# 07_-_eMMC.net
KiCad netlist of a schematic drawn in Altium Designer
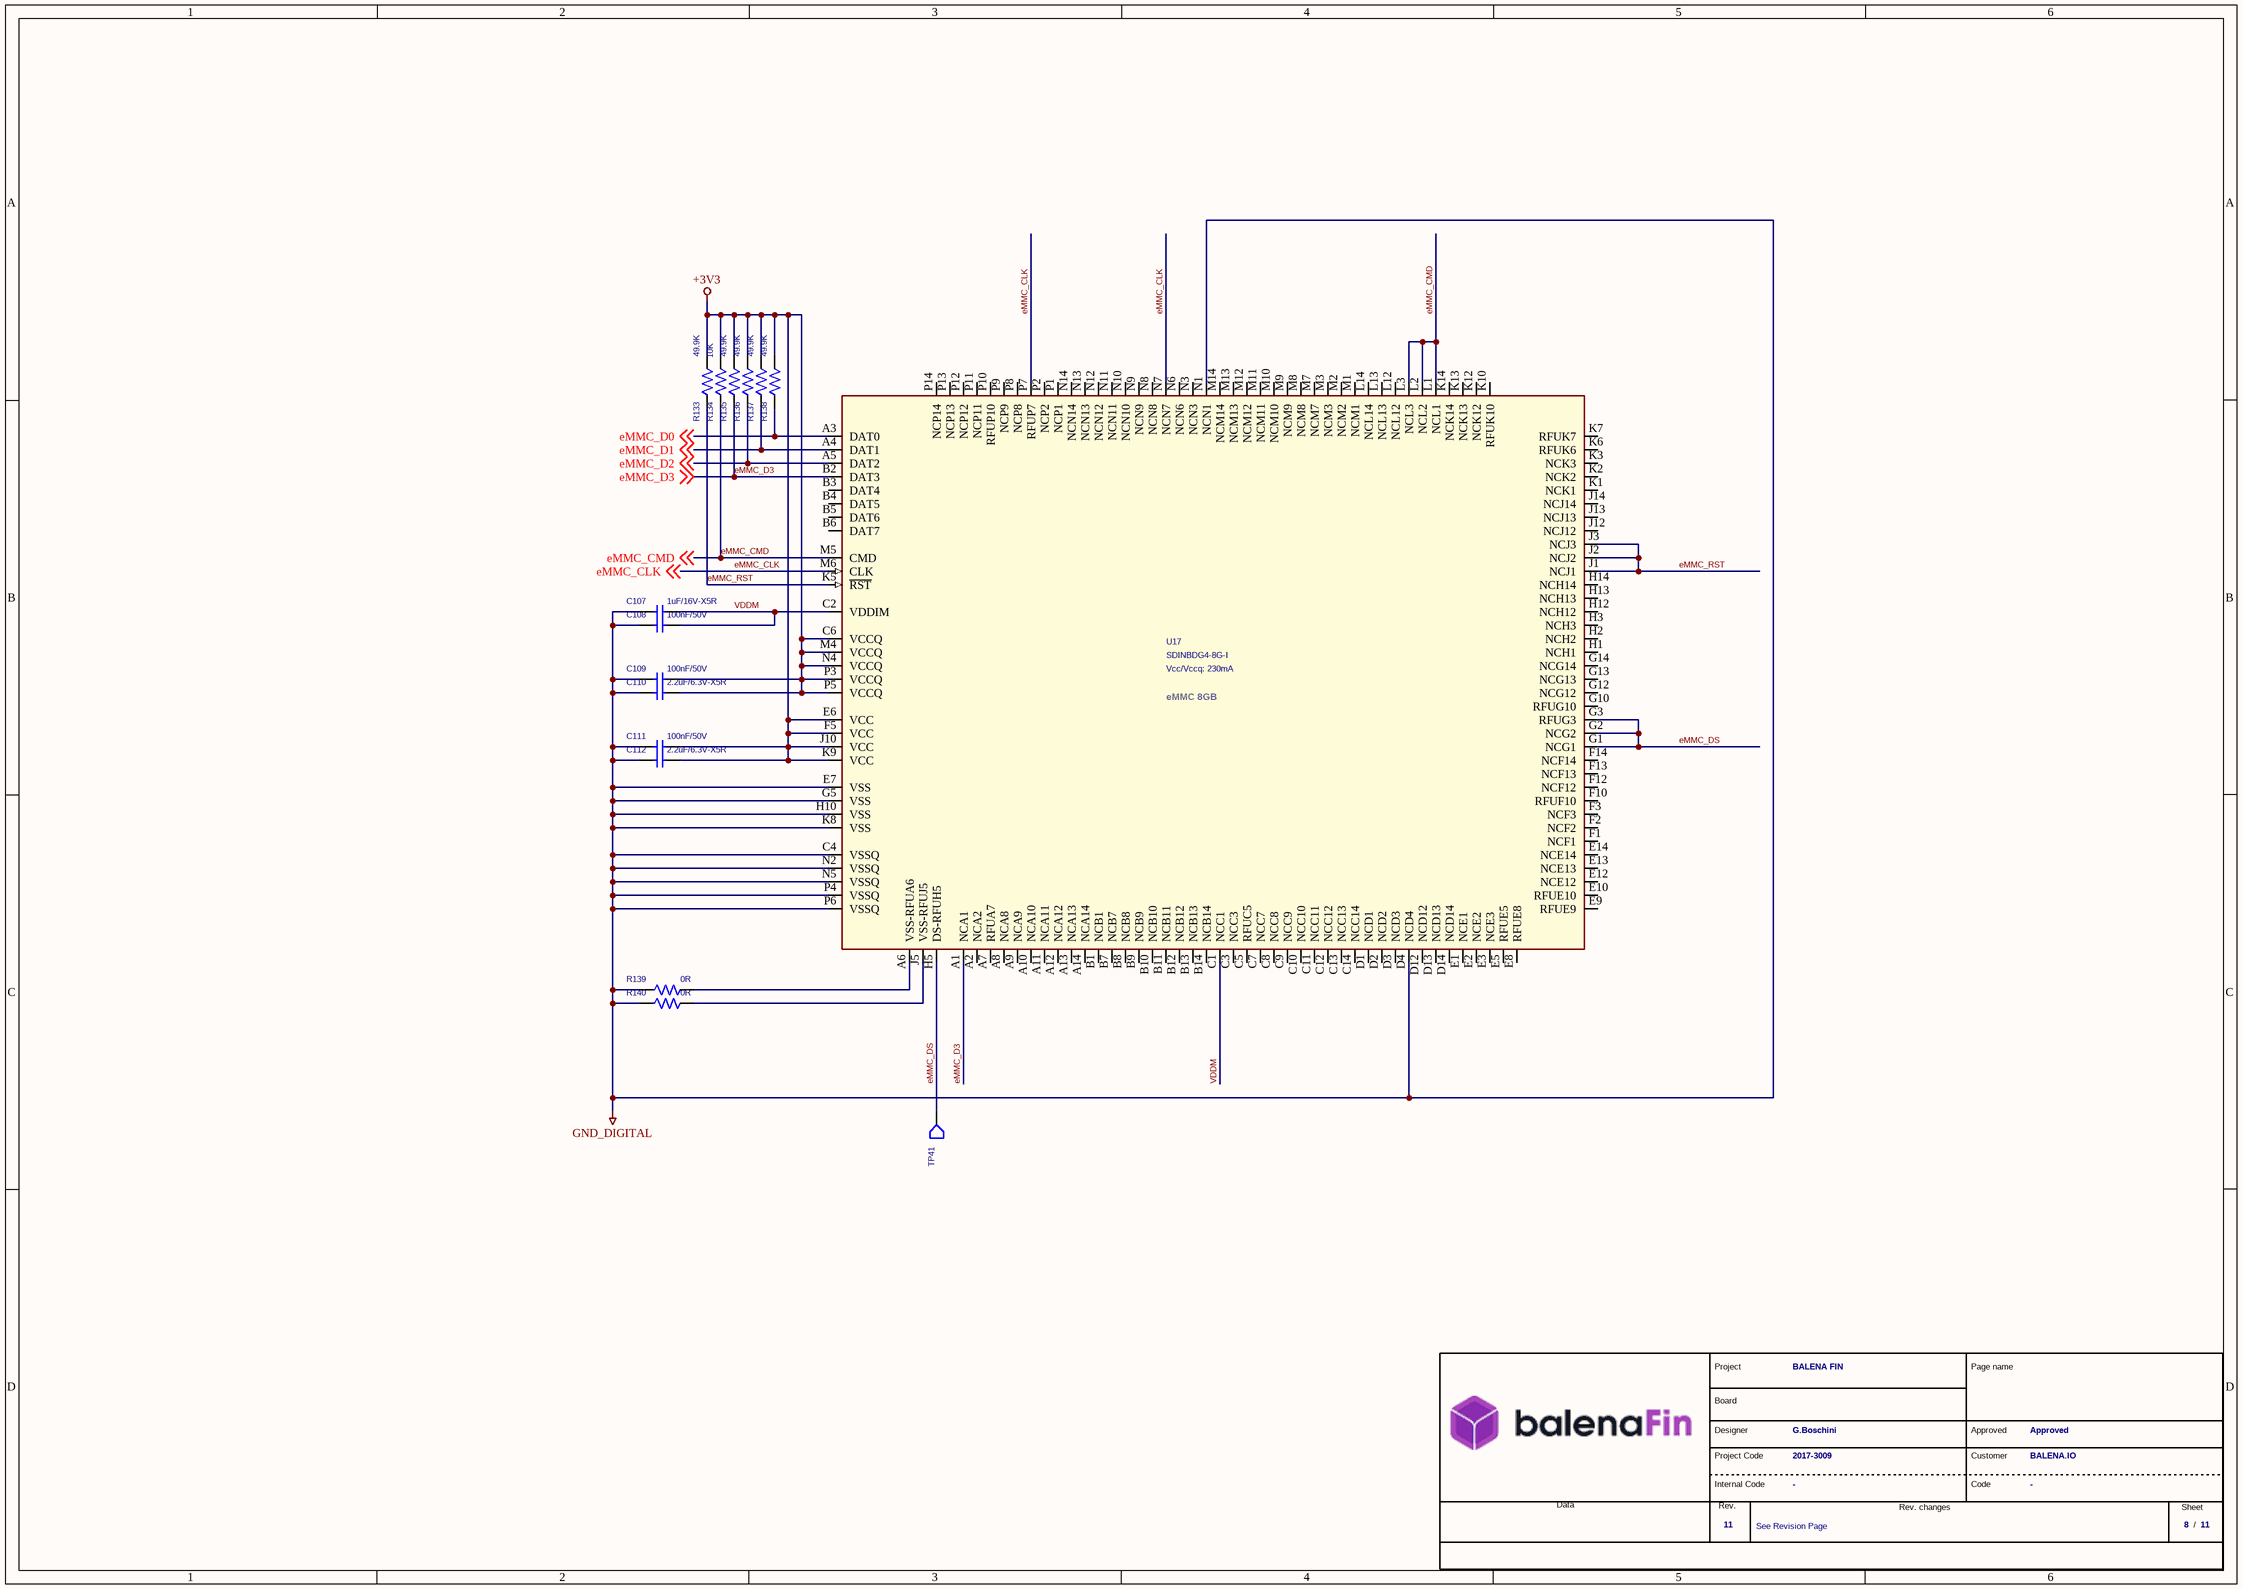
[diagram p0: 07 - eMMC.SchDoc]

(export (version "E")
  (design (tool "Eeschema 10.0.6"))
  (components
    (comp (ref "C107")
      (value "1uF/16V-X5R")
      (footprint "CS-C-0402")
      (description "CHIP CAP.CER. 1uF 16V 10% X5R 0402")
      (fields (field (name "MPN") "Generic"))
      (libsource (lib "*") (part "CS-C-0402-1u/16-X5R"))
    )
    (comp (ref "C108")
      (value "100nF/50V")
      (footprint "CS-C-0402")
      (description "CHIP CAP.CER. 100nF 16V 10% X7R 0402")
      (fields (field (name "MPN") "Generic"))
      (libsource (lib "*") (part "CS-C-0402-100n/16V"))
    )
    (comp (ref "C109")
      (value "100nF/50V")
      (footprint "CS-C-0402")
      (description "CHIP CAP.CER. 100nF 16V 10% X7R 0402")
      (fields (field (name "MPN") "Generic"))
      (libsource (lib "*") (part "CS-C-0402-100n/16V"))
    )
    (comp (ref "C110")
      (value "2.2uF/6.3V-X5R")
      (footprint "CS-C-0402")
      (description "CHIP CAP.CER. 2.2uF 6.3V 20% X5R 0402")
      (fields (field (name "MPN") "Generic"))
      (libsource (lib "*") (part "CS-C-0402-2.2u/6V3-X5R"))
    )
    (comp (ref "C111")
      (value "100nF/50V")
      (footprint "CS-C-0402")
      (description "CHIP CAP.CER. 100nF 16V 10% X7R 0402")
      (fields (field (name "MPN") "Generic"))
      (libsource (lib "*") (part "CS-C-0402-100n/16V"))
    )
    (comp (ref "C112")
      (value "2.2uF/6.3V-X5R")
      (footprint "CS-C-0402")
      (description "CHIP CAP.CER. 2.2uF 6.3V 20% X5R 0402")
      (fields (field (name "MPN") "Generic"))
      (libsource (lib "*") (part "CS-C-0402-2.2u/6V3-X5R"))
    )
    (comp (ref "R133")
      (value "49.9K")
      (footprint "RS-0402")
      (description "CHIP RES. 49K9 0402 1/16W 1% 100PPM/°C")
      (fields (field (name "MPN") "Generic"))
      (libsource (lib "*") (part "RS-0402-49.9k"))
    )
    (comp (ref "R134")
      (value "10K")
      (footprint "RS-0402")
      (description "CHIP RES. 10K 0402 1/16W 1%")
      (fields (field (name "MPN") "Generic"))
      (libsource (lib "*") (part "RS-0402-10k"))
    )
    (comp (ref "R135")
      (value "49.9K")
      (footprint "RS-0402")
      (description "CHIP RES. 49K9 0402 1/16W 1% 100PPM/°C")
      (fields (field (name "MPN") "Generic"))
      (libsource (lib "*") (part "RS-0402-49.9k"))
    )
    (comp (ref "R136")
      (value "49.9K")
      (footprint "RS-0402")
      (description "CHIP RES. 49K9 0402 1/16W 1% 100PPM/°C")
      (fields (field (name "MPN") "Generic"))
      (libsource (lib "*") (part "RS-0402-49.9k"))
    )
    (comp (ref "R137")
      (value "49.9K")
      (footprint "RS-0402")
      (description "CHIP RES. 49K9 0402 1/16W 1% 100PPM/°C")
      (fields (field (name "MPN") "Generic"))
      (libsource (lib "*") (part "RS-0402-49.9k"))
    )
    (comp (ref "R138")
      (value "49.9K")
      (footprint "RS-0402")
      (description "CHIP RES. 49K9 0402 1/16W 1% 100PPM/°C")
      (fields (field (name "MPN") "Generic"))
      (libsource (lib "*") (part "RS-0402-49.9k"))
    )
    (comp (ref "R139")
      (value "0R")
      (footprint "RS-0402")
      (description "CHIP RES. 0R 0402 1/16W 1%")
      (fields (field (name "MPN") "Generic"))
      (libsource (lib "*") (part "RS-0402-0r"))
    )
    (comp (ref "R140")
      (value "0R")
      (footprint "RS-0402")
      (description "CHIP RES. 0R 0402 1/16W 1%")
      (fields (field (name "MPN") "Generic"))
      (libsource (lib "*") (part "RS-0402-0r"))
    )
    (comp (ref "TP41")
      (value "TPS")
      (footprint "TPS-0100")
      (description "TEST POINT SMD")
      (fields (field (name "MPN") "TP-No-BoM"))
      (libsource (lib "*") (part "TEST POINT SMD 1 MM"))
    )
    (comp (ref "U17")
      (value "SDINBDG4-8G-I")
      (footprint "VFBGA153")
      (description "IC eMMC SDINBDG4-8G SANDISK VFBGA153 SMT")
      (fields (field (name "POWER REQUIREMENTS") "Vcc/Vccq: 230mA"))
      (libsource (lib "*") (part "eMMC - SDINBDG4-8G-I - 8GB"))
    )
  )
  (nets
    (net (code "1") (name "+3V3") (class "Default")
      (node (ref "C109") (pin "2") (pinfunction "2_2") (pintype "passive"))
      (node (ref "C110") (pin "2") (pinfunction "2_2") (pintype "passive"))
      (node (ref "C111") (pin "2") (pinfunction "2_2") (pintype "passive"))
      (node (ref "C112") (pin "2") (pinfunction "2_2") (pintype "passive"))
      (node (ref "R133") (pin "2") (pinfunction "2_2") (pintype "passive"))
      (node (ref "R134") (pin "2") (pinfunction "2_2") (pintype "passive"))
      (node (ref "R135") (pin "2") (pinfunction "2_2") (pintype "passive"))
      (node (ref "R136") (pin "2") (pinfunction "2_2") (pintype "passive"))
      (node (ref "R137") (pin "2") (pinfunction "2_2") (pintype "passive"))
      (node (ref "R138") (pin "2") (pinfunction "2_2") (pintype "passive"))
      (node (ref "U17") (pin "C6") (pinfunction "VCCQ_C6") (pintype "power_in"))
      (node (ref "U17") (pin "E6") (pinfunction "VCC_E6") (pintype "power_in"))
      (node (ref "U17") (pin "F5") (pinfunction "VCC_F5") (pintype "power_in"))
      (node (ref "U17") (pin "J10") (pinfunction "VCC_J10") (pintype "power_in"))
      (node (ref "U17") (pin "K9") (pinfunction "VCC_K9") (pintype "power_in"))
      (node (ref "U17") (pin "M4") (pinfunction "VCCQ_M4") (pintype "power_in"))
      (node (ref "U17") (pin "N4") (pinfunction "VCCQ_N4") (pintype "power_in"))
      (node (ref "U17") (pin "P3") (pinfunction "VCCQ_P3") (pintype "power_in"))
      (node (ref "U17") (pin "P5") (pinfunction "VCCQ_P5") (pintype "power_in"))
    )
    (net (code "2") (name "/VDDM") (class "Default")
      (node (ref "C107") (pin "2") (pinfunction "2_2") (pintype "passive"))
      (node (ref "C108") (pin "2") (pinfunction "2_2") (pintype "passive"))
      (node (ref "U17") (pin "C1") (pinfunction "NCC1_C1") (pintype "passive"))
      (node (ref "U17") (pin "C2") (pinfunction "VDDIM_C2") (pintype "passive"))
    )
    (net (code "3") (name "/eMMC_DS") (class "Default")
      (node (ref "TP41") (pin "1") (pinfunction "TP_1") (pintype "passive"))
      (node (ref "U17") (pin "G1") (pinfunction "NCG1_G1") (pintype "passive"))
      (node (ref "U17") (pin "G2") (pinfunction "NCG2_G2") (pintype "passive"))
      (node (ref "U17") (pin "G3") (pinfunction "RFUG3_G3") (pintype "passive"))
      (node (ref "U17") (pin "H5") (pinfunction "DS-RFUH5_H5") (pintype "passive"))
    )
    (net (code "4") (name "/eMMC_RST") (class "Default")
      (node (ref "R133") (pin "1") (pinfunction "1_1") (pintype "passive"))
      (node (ref "U17") (pin "J1") (pinfunction "NCJ1_J1") (pintype "passive"))
      (node (ref "U17") (pin "J2") (pinfunction "NCJ2_J2") (pintype "passive"))
      (node (ref "U17") (pin "J3") (pinfunction "NCJ3_J3") (pintype "passive"))
      (node (ref "U17") (pin "K5") (pinfunction "~{RST}_K5") (pintype "input"))
    )
    (net (code "5") (name "GND_DIGITAL") (class "Default")
      (node (ref "C107") (pin "1") (pinfunction "1_1") (pintype "passive"))
      (node (ref "C108") (pin "1") (pinfunction "1_1") (pintype "passive"))
      (node (ref "C109") (pin "1") (pinfunction "1_1") (pintype "passive"))
      (node (ref "C110") (pin "1") (pinfunction "1_1") (pintype "passive"))
      (node (ref "C111") (pin "1") (pinfunction "1_1") (pintype "passive"))
      (node (ref "C112") (pin "1") (pinfunction "1_1") (pintype "passive"))
      (node (ref "R139") (pin "1") (pinfunction "1_1") (pintype "passive"))
      (node (ref "R140") (pin "1") (pinfunction "1_1") (pintype "passive"))
      (node (ref "U17") (pin "C4") (pinfunction "VSSQ_C4") (pintype "power_in"))
      (node (ref "U17") (pin "D4") (pinfunction "NCD4_D4") (pintype "passive"))
      (node (ref "U17") (pin "E7") (pinfunction "VSS_E7") (pintype "power_in"))
      (node (ref "U17") (pin "G5") (pinfunction "VSS_G5") (pintype "power_in"))
      (node (ref "U17") (pin "H10") (pinfunction "VSS_H10") (pintype "power_in"))
      (node (ref "U17") (pin "K8") (pinfunction "VSS_K8") (pintype "power_in"))
      (node (ref "U17") (pin "N1") (pinfunction "NCN1_N1") (pintype "passive"))
      (node (ref "U17") (pin "N2") (pinfunction "VSSQ_N2") (pintype "power_in"))
      (node (ref "U17") (pin "N5") (pinfunction "VSSQ_N5") (pintype "power_in"))
      (node (ref "U17") (pin "P4") (pinfunction "VSSQ_P4") (pintype "power_in"))
      (node (ref "U17") (pin "P6") (pinfunction "VSSQ_P6") (pintype "power_in"))
    )
    (net (code "6") (name "Net-(U17-VSS-RFUA6)") (class "Default")
      (node (ref "R139") (pin "2") (pinfunction "2_2") (pintype "passive"))
      (node (ref "U17") (pin "A6") (pinfunction "VSS-RFUA6_A6") (pintype "passive"))
    )
    (net (code "7") (name "Net-(U17-VSS-RFUJ5)") (class "Default")
      (node (ref "R140") (pin "2") (pinfunction "2_2") (pintype "passive"))
      (node (ref "U17") (pin "J5") (pinfunction "VSS-RFUJ5_J5") (pintype "passive"))
    )
    (net (code "8") (name "eMMC_CLK") (class "Default")
      (node (ref "U17") (pin "M6") (pinfunction "CLK_M6") (pintype "input"))
      (node (ref "U17") (pin "N7") (pinfunction "NCN7_N7") (pintype "passive"))
      (node (ref "U17") (pin "P7") (pinfunction "RFUP7_P7") (pintype "passive"))
    )
    (net (code "9") (name "eMMC_CMD") (class "Default")
      (node (ref "R134") (pin "1") (pinfunction "1_1") (pintype "passive"))
      (node (ref "U17") (pin "L1") (pinfunction "NCL1_L1") (pintype "passive"))
      (node (ref "U17") (pin "L2") (pinfunction "NCL2_L2") (pintype "passive"))
      (node (ref "U17") (pin "L3") (pinfunction "NCL3_L3") (pintype "passive"))
      (node (ref "U17") (pin "M5") (pinfunction "CMD_M5") (pintype "bidirectional"))
    )
    (net (code "10") (name "eMMC_D0") (class "Default")
      (node (ref "R138") (pin "1") (pinfunction "1_1") (pintype "passive"))
      (node (ref "U17") (pin "A3") (pinfunction "DAT0_A3") (pintype "bidirectional"))
    )
    (net (code "11") (name "eMMC_D1") (class "Default")
      (node (ref "R137") (pin "1") (pinfunction "1_1") (pintype "passive"))
      (node (ref "U17") (pin "A4") (pinfunction "DAT1_A4") (pintype "bidirectional"))
    )
    (net (code "12") (name "eMMC_D2") (class "Default")
      (node (ref "R136") (pin "1") (pinfunction "1_1") (pintype "passive"))
      (node (ref "U17") (pin "A5") (pinfunction "DAT2_A5") (pintype "bidirectional"))
    )
    (net (code "13") (name "eMMC_D3") (class "Default")
      (node (ref "R135") (pin "1") (pinfunction "1_1") (pintype "passive"))
      (node (ref "U17") (pin "A1") (pinfunction "NCA1_A1") (pintype "passive"))
      (node (ref "U17") (pin "B2") (pinfunction "DAT3_B2") (pintype "bidirectional"))
    )
    (net (code "14") (name "unconnected-(U17-DAT4-PadB3)") (class "Default")
      (node (ref "U17") (pin "B3") (pinfunction "DAT4_B3") (pintype "bidirectional"))
    )
    (net (code "15") (name "unconnected-(U17-DAT5-PadB4)") (class "Default")
      (node (ref "U17") (pin "B4") (pinfunction "DAT5_B4") (pintype "bidirectional"))
    )
    (net (code "16") (name "unconnected-(U17-DAT6-PadB5)") (class "Default")
      (node (ref "U17") (pin "B5") (pinfunction "DAT6_B5") (pintype "bidirectional"))
    )
    (net (code "17") (name "unconnected-(U17-DAT7-PadB6)") (class "Default")
      (node (ref "U17") (pin "B6") (pinfunction "DAT7_B6") (pintype "bidirectional"))
    )
    (net (code "18") (name "unconnected-(U17-NCA2-PadA2)") (class "Default")
      (node (ref "U17") (pin "A2") (pinfunction "NCA2_A2") (pintype "passive"))
    )
    (net (code "19") (name "unconnected-(U17-NCA8-PadA8)") (class "Default")
      (node (ref "U17") (pin "A8") (pinfunction "NCA8_A8") (pintype "passive"))
    )
    (net (code "20") (name "unconnected-(U17-NCA9-PadA9)") (class "Default")
      (node (ref "U17") (pin "A9") (pinfunction "NCA9_A9") (pintype "passive"))
    )
    (net (code "21") (name "unconnected-(U17-NCA10-PadA10)") (class "Default")
      (node (ref "U17") (pin "A10") (pinfunction "NCA10_A10") (pintype "passive"))
    )
    (net (code "22") (name "unconnected-(U17-NCA11-PadA11)") (class "Default")
      (node (ref "U17") (pin "A11") (pinfunction "NCA11_A11") (pintype "passive"))
    )
    (net (code "23") (name "unconnected-(U17-NCA12-PadA12)") (class "Default")
      (node (ref "U17") (pin "A12") (pinfunction "NCA12_A12") (pintype "passive"))
    )
    (net (code "24") (name "unconnected-(U17-NCA13-PadA13)") (class "Default")
      (node (ref "U17") (pin "A13") (pinfunction "NCA13_A13") (pintype "passive"))
    )
    (net (code "25") (name "unconnected-(U17-NCA14-PadA14)") (class "Default")
      (node (ref "U17") (pin "A14") (pinfunction "NCA14_A14") (pintype "passive"))
    )
    (net (code "26") (name "unconnected-(U17-NCB1-PadB1)") (class "Default")
      (node (ref "U17") (pin "B1") (pinfunction "NCB1_B1") (pintype "passive"))
    )
    (net (code "27") (name "unconnected-(U17-NCB7-PadB7)") (class "Default")
      (node (ref "U17") (pin "B7") (pinfunction "NCB7_B7") (pintype "passive"))
    )
    (net (code "28") (name "unconnected-(U17-NCB8-PadB8)") (class "Default")
      (node (ref "U17") (pin "B8") (pinfunction "NCB8_B8") (pintype "passive"))
    )
    (net (code "29") (name "unconnected-(U17-NCB9-PadB9)") (class "Default")
      (node (ref "U17") (pin "B9") (pinfunction "NCB9_B9") (pintype "passive"))
    )
    (net (code "30") (name "unconnected-(U17-NCB10-PadB10)") (class "Default")
      (node (ref "U17") (pin "B10") (pinfunction "NCB10_B10") (pintype "passive"))
    )
    (net (code "31") (name "unconnected-(U17-NCB11-PadB11)") (class "Default")
      (node (ref "U17") (pin "B11") (pinfunction "NCB11_B11") (pintype "passive"))
    )
    (net (code "32") (name "unconnected-(U17-NCB12-PadB12)") (class "Default")
      (node (ref "U17") (pin "B12") (pinfunction "NCB12_B12") (pintype "passive"))
    )
    (net (code "33") (name "unconnected-(U17-NCB13-PadB13)") (class "Default")
      (node (ref "U17") (pin "B13") (pinfunction "NCB13_B13") (pintype "passive"))
    )
    (net (code "34") (name "unconnected-(U17-NCB14-PadB14)") (class "Default")
      (node (ref "U17") (pin "B14") (pinfunction "NCB14_B14") (pintype "passive"))
    )
    (net (code "35") (name "unconnected-(U17-NCC3-PadC3)") (class "Default")
      (node (ref "U17") (pin "C3") (pinfunction "NCC3_C3") (pintype "passive"))
    )
    (net (code "36") (name "unconnected-(U17-NCC7-PadC7)") (class "Default")
      (node (ref "U17") (pin "C7") (pinfunction "NCC7_C7") (pintype "passive"))
    )
    (net (code "37") (name "unconnected-(U17-NCC8-PadC8)") (class "Default")
      (node (ref "U17") (pin "C8") (pinfunction "NCC8_C8") (pintype "passive"))
    )
    (net (code "38") (name "unconnected-(U17-NCC9-PadC9)") (class "Default")
      (node (ref "U17") (pin "C9") (pinfunction "NCC9_C9") (pintype "passive"))
    )
    (net (code "39") (name "unconnected-(U17-NCC10-PadC10)") (class "Default")
      (node (ref "U17") (pin "C10") (pinfunction "NCC10_C10") (pintype "passive"))
    )
    (net (code "40") (name "unconnected-(U17-NCC11-PadC11)") (class "Default")
      (node (ref "U17") (pin "C11") (pinfunction "NCC11_C11") (pintype "passive"))
    )
    (net (code "41") (name "unconnected-(U17-NCC12-PadC12)") (class "Default")
      (node (ref "U17") (pin "C12") (pinfunction "NCC12_C12") (pintype "passive"))
    )
    (net (code "42") (name "unconnected-(U17-NCC13-PadC13)") (class "Default")
      (node (ref "U17") (pin "C13") (pinfunction "NCC13_C13") (pintype "passive"))
    )
    (net (code "43") (name "unconnected-(U17-NCC14-PadC14)") (class "Default")
      (node (ref "U17") (pin "C14") (pinfunction "NCC14_C14") (pintype "passive"))
    )
    (net (code "44") (name "unconnected-(U17-NCD1-PadD1)") (class "Default")
      (node (ref "U17") (pin "D1") (pinfunction "NCD1_D1") (pintype "passive"))
    )
    (net (code "45") (name "unconnected-(U17-NCD2-PadD2)") (class "Default")
      (node (ref "U17") (pin "D2") (pinfunction "NCD2_D2") (pintype "passive"))
    )
    (net (code "46") (name "unconnected-(U17-NCD3-PadD3)") (class "Default")
      (node (ref "U17") (pin "D3") (pinfunction "NCD3_D3") (pintype "passive"))
    )
    (net (code "47") (name "unconnected-(U17-NCD12-PadD12)") (class "Default")
      (node (ref "U17") (pin "D12") (pinfunction "NCD12_D12") (pintype "passive"))
    )
    (net (code "48") (name "unconnected-(U17-NCD13-PadD13)") (class "Default")
      (node (ref "U17") (pin "D13") (pinfunction "NCD13_D13") (pintype "passive"))
    )
    (net (code "49") (name "unconnected-(U17-NCD14-PadD14)") (class "Default")
      (node (ref "U17") (pin "D14") (pinfunction "NCD14_D14") (pintype "passive"))
    )
    (net (code "50") (name "unconnected-(U17-NCE1-PadE1)") (class "Default")
      (node (ref "U17") (pin "E1") (pinfunction "NCE1_E1") (pintype "passive"))
    )
    (net (code "51") (name "unconnected-(U17-NCE2-PadE2)") (class "Default")
      (node (ref "U17") (pin "E2") (pinfunction "NCE2_E2") (pintype "passive"))
    )
    (net (code "52") (name "unconnected-(U17-NCE3-PadE3)") (class "Default")
      (node (ref "U17") (pin "E3") (pinfunction "NCE3_E3") (pintype "passive"))
    )
    (net (code "53") (name "unconnected-(U17-NCE12-PadE12)") (class "Default")
      (node (ref "U17") (pin "E12") (pinfunction "NCE12_E12") (pintype "passive"))
    )
    (net (code "54") (name "unconnected-(U17-NCE13-PadE13)") (class "Default")
      (node (ref "U17") (pin "E13") (pinfunction "NCE13_E13") (pintype "passive"))
    )
    (net (code "55") (name "unconnected-(U17-NCE14-PadE14)") (class "Default")
      (node (ref "U17") (pin "E14") (pinfunction "NCE14_E14") (pintype "passive"))
    )
    (net (code "56") (name "unconnected-(U17-NCF1-PadF1)") (class "Default")
      (node (ref "U17") (pin "F1") (pinfunction "NCF1_F1") (pintype "passive"))
    )
    (net (code "57") (name "unconnected-(U17-NCF2-PadF2)") (class "Default")
      (node (ref "U17") (pin "F2") (pinfunction "NCF2_F2") (pintype "passive"))
    )
    (net (code "58") (name "unconnected-(U17-NCF3-PadF3)") (class "Default")
      (node (ref "U17") (pin "F3") (pinfunction "NCF3_F3") (pintype "passive"))
    )
    (net (code "59") (name "unconnected-(U17-NCF12-PadF12)") (class "Default")
      (node (ref "U17") (pin "F12") (pinfunction "NCF12_F12") (pintype "passive"))
    )
    (net (code "60") (name "unconnected-(U17-NCF13-PadF13)") (class "Default")
      (node (ref "U17") (pin "F13") (pinfunction "NCF13_F13") (pintype "passive"))
    )
    (net (code "61") (name "unconnected-(U17-NCF14-PadF14)") (class "Default")
      (node (ref "U17") (pin "F14") (pinfunction "NCF14_F14") (pintype "passive"))
    )
    (net (code "62") (name "unconnected-(U17-NCG12-PadG12)") (class "Default")
      (node (ref "U17") (pin "G12") (pinfunction "NCG12_G12") (pintype "passive"))
    )
    (net (code "63") (name "unconnected-(U17-NCG13-PadG13)") (class "Default")
      (node (ref "U17") (pin "G13") (pinfunction "NCG13_G13") (pintype "passive"))
    )
    (net (code "64") (name "unconnected-(U17-NCG14-PadG14)") (class "Default")
      (node (ref "U17") (pin "G14") (pinfunction "NCG14_G14") (pintype "passive"))
    )
    (net (code "65") (name "unconnected-(U17-NCH1-PadH1)") (class "Default")
      (node (ref "U17") (pin "H1") (pinfunction "NCH1_H1") (pintype "passive"))
    )
    (net (code "66") (name "unconnected-(U17-NCH2-PadH2)") (class "Default")
      (node (ref "U17") (pin "H2") (pinfunction "NCH2_H2") (pintype "passive"))
    )
    (net (code "67") (name "unconnected-(U17-NCH3-PadH3)") (class "Default")
      (node (ref "U17") (pin "H3") (pinfunction "NCH3_H3") (pintype "passive"))
    )
    (net (code "68") (name "unconnected-(U17-NCH12-PadH12)") (class "Default")
      (node (ref "U17") (pin "H12") (pinfunction "NCH12_H12") (pintype "passive"))
    )
    (net (code "69") (name "unconnected-(U17-NCH13-PadH13)") (class "Default")
      (node (ref "U17") (pin "H13") (pinfunction "NCH13_H13") (pintype "passive"))
    )
    (net (code "70") (name "unconnected-(U17-NCH14-PadH14)") (class "Default")
      (node (ref "U17") (pin "H14") (pinfunction "NCH14_H14") (pintype "passive"))
    )
    (net (code "71") (name "unconnected-(U17-NCJ12-PadJ12)") (class "Default")
      (node (ref "U17") (pin "J12") (pinfunction "NCJ12_J12") (pintype "passive"))
    )
    (net (code "72") (name "unconnected-(U17-NCJ13-PadJ13)") (class "Default")
      (node (ref "U17") (pin "J13") (pinfunction "NCJ13_J13") (pintype "passive"))
    )
    (net (code "73") (name "unconnected-(U17-NCJ14-PadJ14)") (class "Default")
      (node (ref "U17") (pin "J14") (pinfunction "NCJ14_J14") (pintype "passive"))
    )
    (net (code "74") (name "unconnected-(U17-NCK1-PadK1)") (class "Default")
      (node (ref "U17") (pin "K1") (pinfunction "NCK1_K1") (pintype "passive"))
    )
    (net (code "75") (name "unconnected-(U17-NCK2-PadK2)") (class "Default")
      (node (ref "U17") (pin "K2") (pinfunction "NCK2_K2") (pintype "passive"))
    )
    (net (code "76") (name "unconnected-(U17-NCK3-PadK3)") (class "Default")
      (node (ref "U17") (pin "K3") (pinfunction "NCK3_K3") (pintype "passive"))
    )
    (net (code "77") (name "unconnected-(U17-NCK12-PadK12)") (class "Default")
      (node (ref "U17") (pin "K12") (pinfunction "NCK12_K12") (pintype "passive"))
    )
    (net (code "78") (name "unconnected-(U17-NCK13-PadK13)") (class "Default")
      (node (ref "U17") (pin "K13") (pinfunction "NCK13_K13") (pintype "passive"))
    )
    (net (code "79") (name "unconnected-(U17-NCK14-PadK14)") (class "Default")
      (node (ref "U17") (pin "K14") (pinfunction "NCK14_K14") (pintype "passive"))
    )
    (net (code "80") (name "unconnected-(U17-NCL12-PadL12)") (class "Default")
      (node (ref "U17") (pin "L12") (pinfunction "NCL12_L12") (pintype "passive"))
    )
    (net (code "81") (name "unconnected-(U17-NCL13-PadL13)") (class "Default")
      (node (ref "U17") (pin "L13") (pinfunction "NCL13_L13") (pintype "passive"))
    )
    (net (code "82") (name "unconnected-(U17-NCL14-PadL14)") (class "Default")
      (node (ref "U17") (pin "L14") (pinfunction "NCL14_L14") (pintype "passive"))
    )
    (net (code "83") (name "unconnected-(U17-NCM1-PadM1)") (class "Default")
      (node (ref "U17") (pin "M1") (pinfunction "NCM1_M1") (pintype "passive"))
    )
    (net (code "84") (name "unconnected-(U17-NCM2-PadM2)") (class "Default")
      (node (ref "U17") (pin "M2") (pinfunction "NCM2_M2") (pintype "passive"))
    )
    (net (code "85") (name "unconnected-(U17-NCM3-PadM3)") (class "Default")
      (node (ref "U17") (pin "M3") (pinfunction "NCM3_M3") (pintype "passive"))
    )
    (net (code "86") (name "unconnected-(U17-NCM7-PadM7)") (class "Default")
      (node (ref "U17") (pin "M7") (pinfunction "NCM7_M7") (pintype "passive"))
    )
    (net (code "87") (name "unconnected-(U17-NCM8-PadM8)") (class "Default")
      (node (ref "U17") (pin "M8") (pinfunction "NCM8_M8") (pintype "passive"))
    )
    (net (code "88") (name "unconnected-(U17-NCM9-PadM9)") (class "Default")
      (node (ref "U17") (pin "M9") (pinfunction "NCM9_M9") (pintype "passive"))
    )
    (net (code "89") (name "unconnected-(U17-NCM10-PadM10)") (class "Default")
      (node (ref "U17") (pin "M10") (pinfunction "NCM10_M10") (pintype "passive"))
    )
    (net (code "90") (name "unconnected-(U17-NCM11-PadM11)") (class "Default")
      (node (ref "U17") (pin "M11") (pinfunction "NCM11_M11") (pintype "passive"))
    )
    (net (code "91") (name "unconnected-(U17-NCM12-PadM12)") (class "Default")
      (node (ref "U17") (pin "M12") (pinfunction "NCM12_M12") (pintype "passive"))
    )
    (net (code "92") (name "unconnected-(U17-NCM13-PadM13)") (class "Default")
      (node (ref "U17") (pin "M13") (pinfunction "NCM13_M13") (pintype "passive"))
    )
    (net (code "93") (name "unconnected-(U17-NCM14-PadM14)") (class "Default")
      (node (ref "U17") (pin "M14") (pinfunction "NCM14_M14") (pintype "passive"))
    )
    (net (code "94") (name "unconnected-(U17-NCN3-PadN3)") (class "Default")
      (node (ref "U17") (pin "N3") (pinfunction "NCN3_N3") (pintype "passive"))
    )
    (net (code "95") (name "unconnected-(U17-NCN6-PadN6)") (class "Default")
      (node (ref "U17") (pin "N6") (pinfunction "NCN6_N6") (pintype "passive"))
    )
    (net (code "96") (name "unconnected-(U17-NCN8-PadN8)") (class "Default")
      (node (ref "U17") (pin "N8") (pinfunction "NCN8_N8") (pintype "passive"))
    )
    (net (code "97") (name "unconnected-(U17-NCN9-PadN9)") (class "Default")
      (node (ref "U17") (pin "N9") (pinfunction "NCN9_N9") (pintype "passive"))
    )
    (net (code "98") (name "unconnected-(U17-NCN10-PadN10)") (class "Default")
      (node (ref "U17") (pin "N10") (pinfunction "NCN10_N10") (pintype "passive"))
    )
    (net (code "99") (name "unconnected-(U17-NCN11-PadN11)") (class "Default")
      (node (ref "U17") (pin "N11") (pinfunction "NCN11_N11") (pintype "passive"))
    )
    (net (code "100") (name "unconnected-(U17-NCN12-PadN12)") (class "Default")
      (node (ref "U17") (pin "N12") (pinfunction "NCN12_N12") (pintype "passive"))
    )
    (net (code "101") (name "unconnected-(U17-NCN13-PadN13)") (class "Default")
      (node (ref "U17") (pin "N13") (pinfunction "NCN13_N13") (pintype "passive"))
    )
    (net (code "102") (name "unconnected-(U17-NCN14-PadN14)") (class "Default")
      (node (ref "U17") (pin "N14") (pinfunction "NCN14_N14") (pintype "passive"))
    )
    (net (code "103") (name "unconnected-(U17-NCP1-PadP1)") (class "Default")
      (node (ref "U17") (pin "P1") (pinfunction "NCP1_P1") (pintype "passive"))
    )
    (net (code "104") (name "unconnected-(U17-NCP2-PadP2)") (class "Default")
      (node (ref "U17") (pin "P2") (pinfunction "NCP2_P2") (pintype "passive"))
    )
    (net (code "105") (name "unconnected-(U17-NCP8-PadP8)") (class "Default")
      (node (ref "U17") (pin "P8") (pinfunction "NCP8_P8") (pintype "passive"))
    )
    (net (code "106") (name "unconnected-(U17-NCP9-PadP9)") (class "Default")
      (node (ref "U17") (pin "P9") (pinfunction "NCP9_P9") (pintype "passive"))
    )
    (net (code "107") (name "unconnected-(U17-NCP11-PadP11)") (class "Default")
      (node (ref "U17") (pin "P11") (pinfunction "NCP11_P11") (pintype "passive"))
    )
    (net (code "108") (name "unconnected-(U17-NCP12-PadP12)") (class "Default")
      (node (ref "U17") (pin "P12") (pinfunction "NCP12_P12") (pintype "passive"))
    )
    (net (code "109") (name "unconnected-(U17-NCP13-PadP13)") (class "Default")
      (node (ref "U17") (pin "P13") (pinfunction "NCP13_P13") (pintype "passive"))
    )
    (net (code "110") (name "unconnected-(U17-NCP14-PadP14)") (class "Default")
      (node (ref "U17") (pin "P14") (pinfunction "NCP14_P14") (pintype "passive"))
    )
    (net (code "111") (name "unconnected-(U17-RFUA7-PadA7)") (class "Default")
      (node (ref "U17") (pin "A7") (pinfunction "RFUA7_A7") (pintype "passive"))
    )
    (net (code "112") (name "unconnected-(U17-RFUC5-PadC5)") (class "Default")
      (node (ref "U17") (pin "C5") (pinfunction "RFUC5_C5") (pintype "passive"))
    )
    (net (code "113") (name "unconnected-(U17-RFUE5-PadE5)") (class "Default")
      (node (ref "U17") (pin "E5") (pinfunction "RFUE5_E5") (pintype "passive"))
    )
    (net (code "114") (name "unconnected-(U17-RFUE8-PadE8)") (class "Default")
      (node (ref "U17") (pin "E8") (pinfunction "RFUE8_E8") (pintype "passive"))
    )
    (net (code "115") (name "unconnected-(U17-RFUE9-PadE9)") (class "Default")
      (node (ref "U17") (pin "E9") (pinfunction "RFUE9_E9") (pintype "passive"))
    )
    (net (code "116") (name "unconnected-(U17-RFUE10-PadE10)") (class "Default")
      (node (ref "U17") (pin "E10") (pinfunction "RFUE10_E10") (pintype "passive"))
    )
    (net (code "117") (name "unconnected-(U17-RFUF10-PadF10)") (class "Default")
      (node (ref "U17") (pin "F10") (pinfunction "RFUF10_F10") (pintype "passive"))
    )
    (net (code "118") (name "unconnected-(U17-RFUG10-PadG10)") (class "Default")
      (node (ref "U17") (pin "G10") (pinfunction "RFUG10_G10") (pintype "passive"))
    )
    (net (code "119") (name "unconnected-(U17-RFUK6-PadK6)") (class "Default")
      (node (ref "U17") (pin "K6") (pinfunction "RFUK6_K6") (pintype "passive"))
    )
    (net (code "120") (name "unconnected-(U17-RFUK7-PadK7)") (class "Default")
      (node (ref "U17") (pin "K7") (pinfunction "RFUK7_K7") (pintype "passive"))
    )
    (net (code "121") (name "unconnected-(U17-RFUK10-PadK10)") (class "Default")
      (node (ref "U17") (pin "K10") (pinfunction "RFUK10_K10") (pintype "passive"))
    )
    (net (code "122") (name "unconnected-(U17-RFUP10-PadP10)") (class "Default")
      (node (ref "U17") (pin "P10") (pinfunction "RFUP10_P10") (pintype "passive"))
    )
  )
)
